# Advanced-filament-RunOut-Sensor.net
KiCad netlist of a schematic drawn in EasyEDA Pro
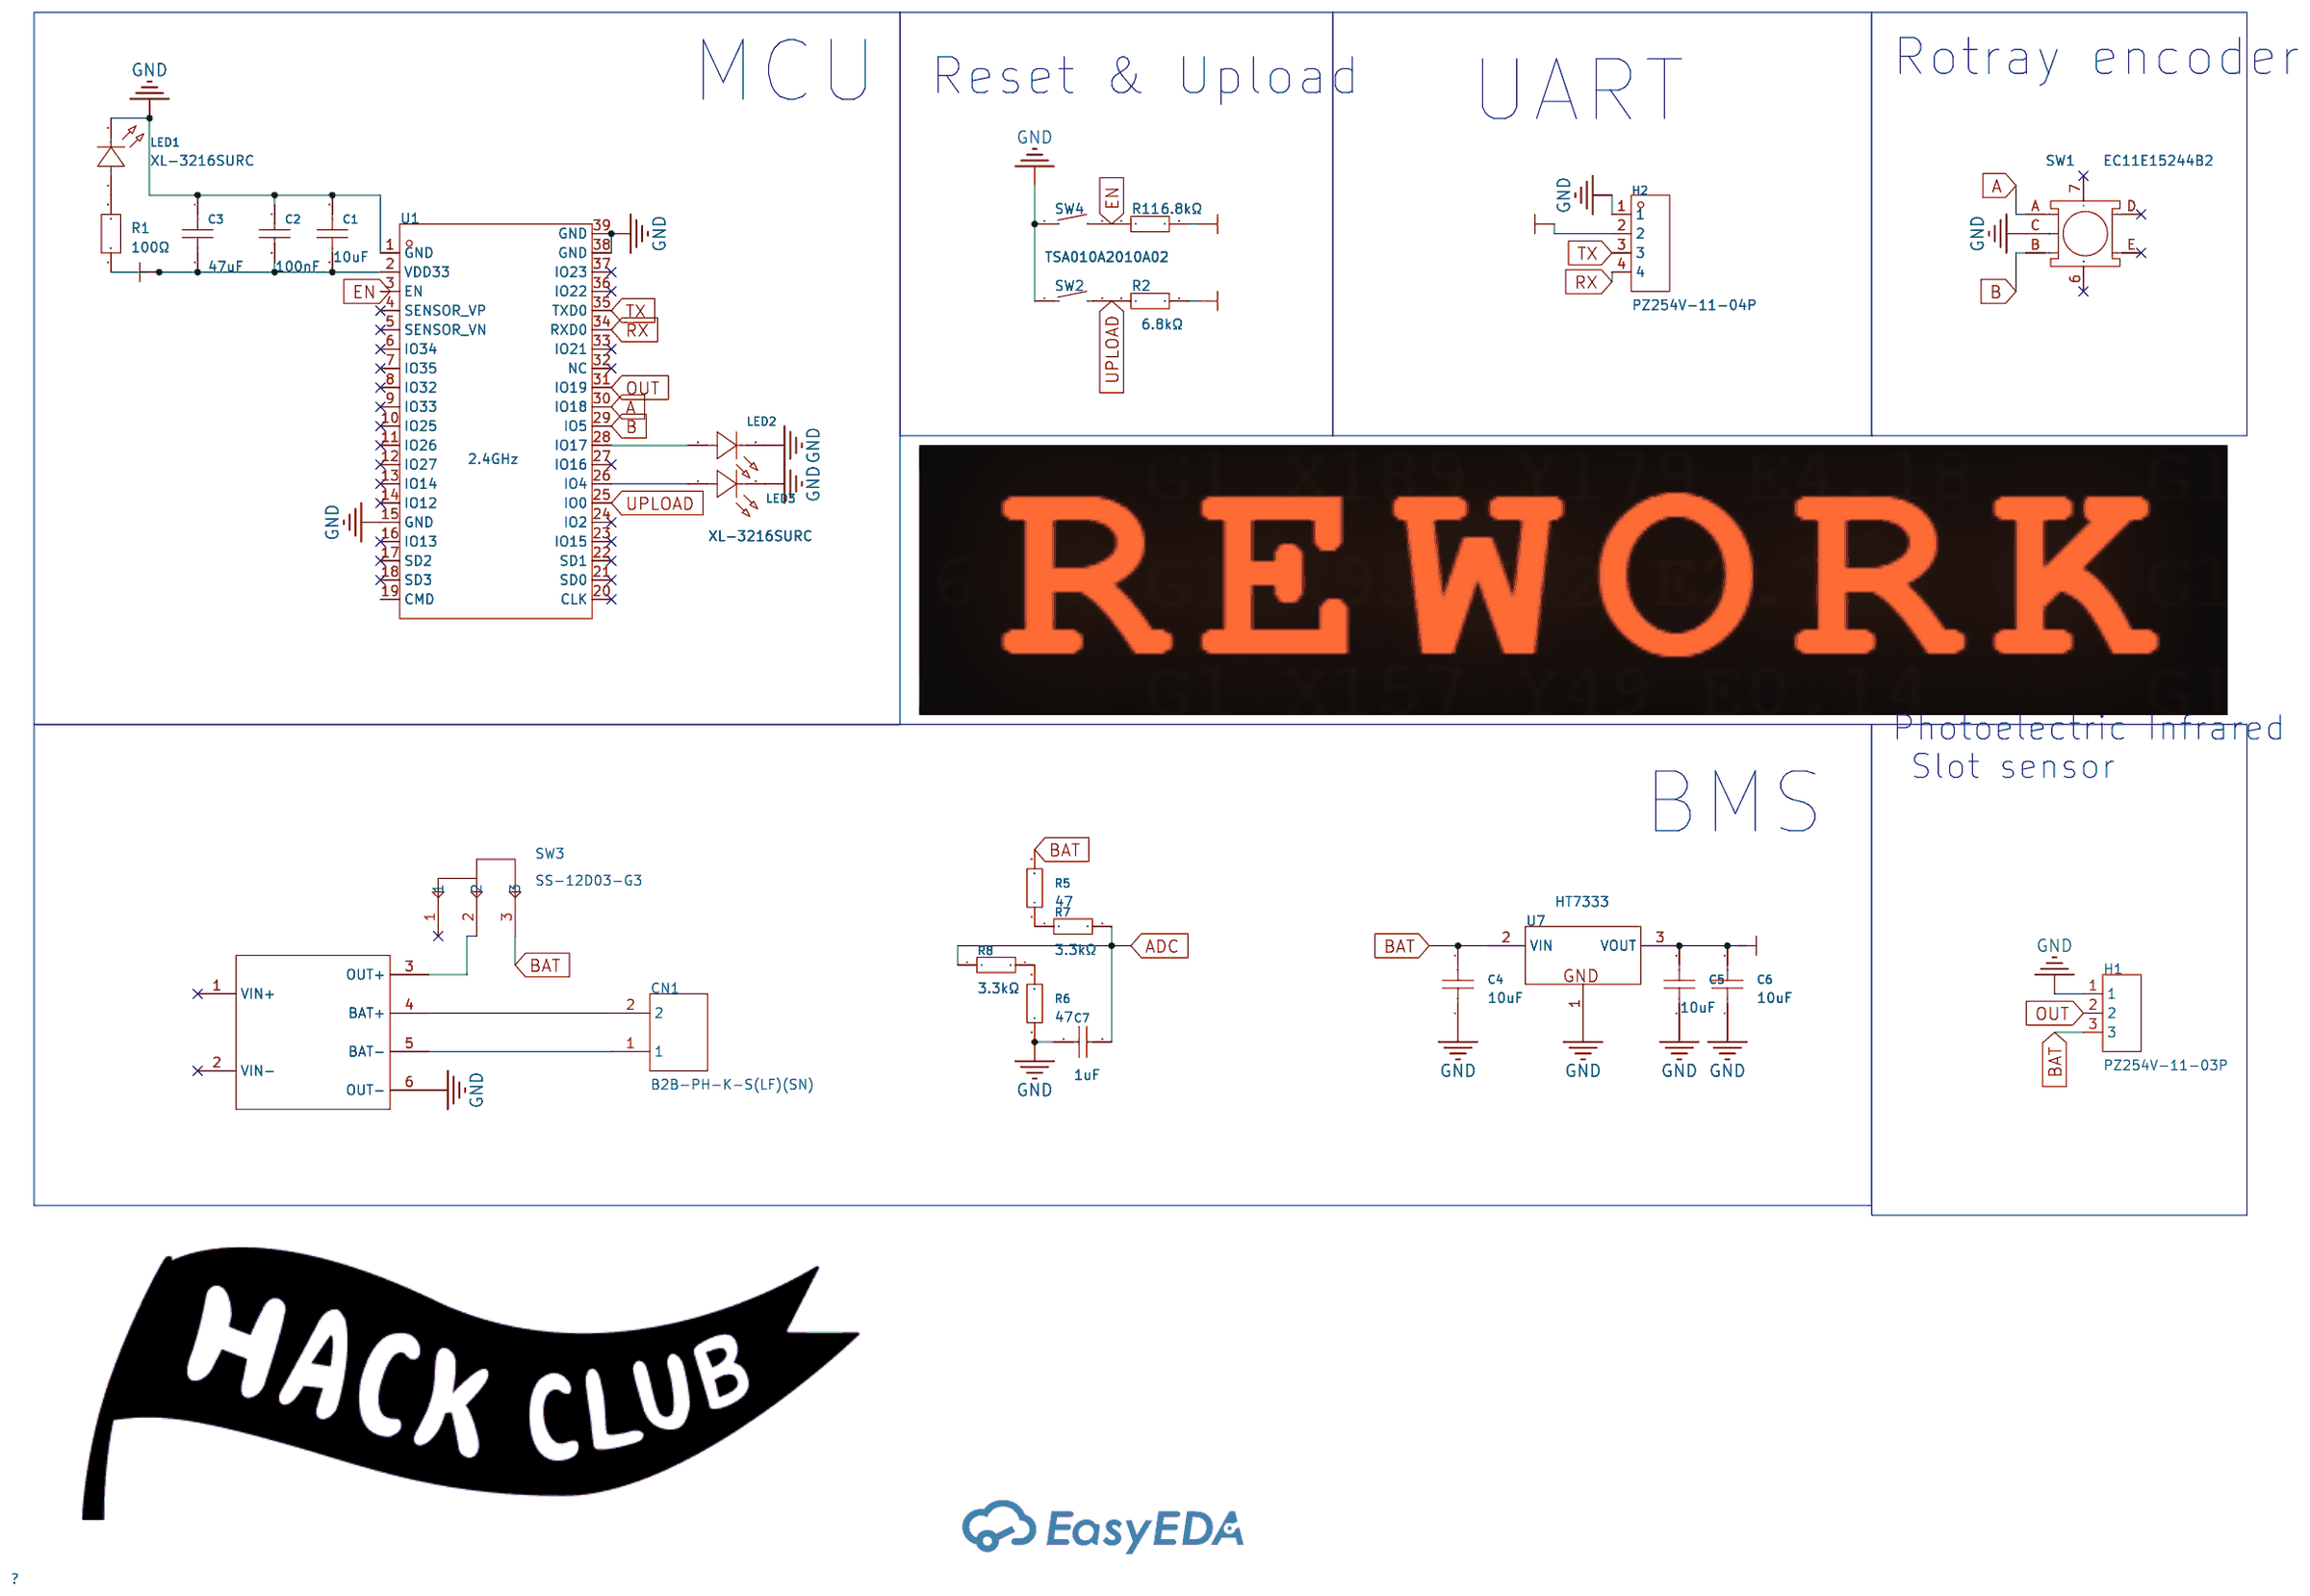
[diagram p0: schematic sheet]

(export (version "E")
  (design (tool "Eeschema 10.0.6"))
  (components
    (comp (ref "C1")
      (value "10uF")
      (footprint "easyedapro:C1206")
      (description "Capacitance:10uF Tolerance:±10% Tolerance:±10% Voltage Rating:16V Temperature Coefficient:X7R")
      (fields (field (name "Manufacturer Part") "1206B106K160CT") (field (name "Manufacturer") "Walsin(华新科)"))
      (libsource (lib "easyedapro") (part "1206B106K160"))
    )
    (comp (ref "C2")
      (value "100nF")
      (footprint "easyedapro:C1206")
      (description "Capacitance:100nF Tolerance:±10% Tolerance:±10% Voltage Rating:50V Temperature Coefficient:X7R")
      (fields
        (field (name "Manufacturer Part") "CL31B104KBCNNNC")
        (field (name "Manufacturer") "SAMSUNG(三星)")
      )
      (libsource (lib "easyedapro") (part "CL31B104KBCNNNC"))
    )
    (comp (ref "C3")
      (value "47uF")
      (footprint "easyedapro:C1206")
      (description "Capacitance:10uF Tolerance:±10% Tolerance:±10% Voltage Rating:16V Temperature Coefficient:X7R")
      (fields (field (name "Manufacturer Part") "1206B106K160CT") (field (name "Manufacturer") "Walsin(华新科)"))
      (libsource (lib "easyedapro") (part "1206B106K160"))
    )
    (comp (ref "C4")
      (value "10uF")
      (footprint "easyedapro:C0603")
      (description "Capacitance:10uF Tolerance:±20% Tolerance:±20% Voltage Rating:25V Temperature Coefficient:X5R")
      (fields
        (field (name "Manufacturer Part") "CL10A106MA8NRNC")
        (field (name "Manufacturer") "SAMSUNG(三星)")
      )
      (libsource (lib "easyedapro") (part "CL10A106MA8NRNC"))
    )
    (comp (ref "C5")
      (value "10uF")
      (footprint "easyedapro:C0603")
      (description "Capacitance:10uF Tolerance:±20% Tolerance:±20% Voltage Rating:25V Temperature Coefficient:X5R")
      (fields
        (field (name "Manufacturer Part") "CL10A106MA8NRNC")
        (field (name "Manufacturer") "SAMSUNG(三星)")
      )
      (libsource (lib "easyedapro") (part "CL10A106MA8NRNC"))
    )
    (comp (ref "C6")
      (value "10uF")
      (footprint "easyedapro:C0603")
      (description "Capacitance:10uF Tolerance:±20% Tolerance:±20% Voltage Rating:25V Temperature Coefficient:X5R")
      (fields
        (field (name "Manufacturer Part") "CL10A106MA8NRNC")
        (field (name "Manufacturer") "SAMSUNG(三星)")
      )
      (libsource (lib "easyedapro") (part "CL10A106MA8NRNC"))
    )
    (comp (ref "C7")
      (value "1uF")
      (footprint "easyedapro:C0805")
      (description "Capacitance:1uF Tolerance:±10% Tolerance:±10% Voltage Rating:50V Temperature Coefficient:X7R")
      (fields
        (field (name "Manufacturer Part") "CL21B105KBFNNNE")
        (field (name "Manufacturer") "SAMSUNG(三星)")
      )
      (libsource (lib "easyedapro") (part "CL21B105KBFNNNE"))
    )
    (comp (ref "CN1")
      (value "B2B-PH-K-S(LF)(SN)")
      (footprint "easyedapro:CONN-TH_B2B-PH-K-S")
      (fields (field (name "Manufacturer") "JST"))
      (libsource (lib "easyedapro") (part "B2B-PH-K-S(LF)(SN)"))
    )
    (comp (ref "H1")
      (value "PZ254V-11-03P")
      (footprint "easyedapro:HDR-TH_3P-P2.54-V-M_PZ254V-11-03P")
      (fields (field (name "Manufacturer") "XFCN(兴飞)"))
      (libsource (lib "easyedapro") (part "PZ254V-11-03P_C2937625"))
    )
    (comp (ref "H2")
      (value "PZ254V-11-04P")
      (footprint "easyedapro:HDR-TH_4P-P2.54-V-M")
      (fields (field (name "Manufacturer") "XFCN(兴飞)"))
      (libsource (lib "easyedapro") (part "PZ254V-11-04P_C2691448"))
    )
    (comp (ref "LED1")
      (value "XL-3216SURC")
      (footprint "easyedapro:LED1206-R-RD_RED")
      (fields (field (name "Manufacturer") "XINGLIGHT(成兴光)"))
      (libsource (lib "easyedapro") (part "XL-3216SURC"))
    )
    (comp (ref "LED2")
      (value "XL-3216SURC")
      (footprint "easyedapro:LED1206-R-RD_RED")
      (fields (field (name "Manufacturer") "XINGLIGHT(成兴光)"))
      (libsource (lib "easyedapro") (part "XL-3216SURC"))
    )
    (comp (ref "LED3")
      (value "XL-3216SURC")
      (footprint "easyedapro:LED1206-R-RD_RED")
      (fields (field (name "Manufacturer") "XINGLIGHT(成兴光)"))
      (libsource (lib "easyedapro") (part "XL-3216SURC"))
    )
    (comp (ref "R1")
      (value "100Ω")
      (footprint "easyedapro:R1206")
      (fields (field (name "Manufacturer Part") "FRC1206F1000TS") (field (name "Manufacturer") "FOJAN(富捷)"))
      (libsource (lib "easyedapro") (part "FRC1206F1000TS"))
    )
    (comp (ref "R2")
      (value "6.8kΩ")
      (footprint "easyedapro:R0603")
      (fields (field (name "Manufacturer Part") "RC0603FR-071KL") (field (name "Manufacturer") "YAGEO(国巨)"))
      (libsource (lib "easyedapro") (part "RC0603FR-071KL"))
    )
    (comp (ref "R5")
      (value "47")
      (footprint "easyedapro:R1206")
      (fields
        (field (name "Manufacturer Part") "1206W4F100KT5E")
        (field (name "Manufacturer") "UNI-ROYAL(厚声)")
      )
      (libsource (lib "easyedapro") (part "1206W4F100KT5E"))
    )
    (comp (ref "R6")
      (value "47")
      (footprint "easyedapro:R1206")
      (fields
        (field (name "Manufacturer Part") "1206W4F100KT5E")
        (field (name "Manufacturer") "UNI-ROYAL(厚声)")
      )
      (libsource (lib "easyedapro") (part "1206W4F100KT5E"))
    )
    (comp (ref "R7")
      (value "3.3kΩ")
      (footprint "easyedapro:R0603")
      (fields
        (field (name "Manufacturer Part") "0603WAF3301T5E")
        (field (name "Manufacturer") "UNI-ROYAL(厚声)")
      )
      (libsource (lib "easyedapro") (part "0603WAF3301T5E"))
    )
    (comp (ref "R8")
      (value "3.3kΩ")
      (footprint "easyedapro:R0603")
      (fields
        (field (name "Manufacturer Part") "0603WAF3301T5E")
        (field (name "Manufacturer") "UNI-ROYAL(厚声)")
      )
      (libsource (lib "easyedapro") (part "0603WAF3301T5E"))
    )
    (comp (ref "R11")
      (value "6.8kΩ")
      (footprint "easyedapro:R0603")
      (fields (field (name "Manufacturer Part") "RC0603FR-071KL") (field (name "Manufacturer") "YAGEO(国巨)"))
      (libsource (lib "easyedapro") (part "RC0603FR-071KL"))
    )
    (comp (ref "SW1")
      (value "EC11E15244B2")
      (footprint "easyedapro:SW-TH_EC11XXXXXXXX")
      (fields (field (name "Manufacturer") "ALPSALPINE(阿尔卑斯阿尔派)"))
      (libsource (lib "easyedapro") (part "EC11E15244B2"))
    )
    (comp (ref "SW2")
      (value "TSA010A2010A02")
      (footprint "easyedapro:KEY-SMD_L3.9-W3.0-LS5.0")
      (fields (field (name "Manufacturer") "BZCN(博众电气)"))
      (libsource (lib "easyedapro") (part "TSA010A2010A02"))
    )
    (comp (ref "SW3")
      (value "SS-12D03-G3")
      (footprint "easyedapro:SW-TH_3P-L8.5-W3.5-P2.50_SS-12D03-G3_C5160828")
      (fields (field (name "Manufacturer") "DEALON(德艺隆)"))
      (libsource (lib "easyedapro") (part "SS-12D03-G3_C5160828"))
    )
    (comp (ref "SW4")
      (value "TSA010A2010A02")
      (footprint "easyedapro:KEY-SMD_L3.9-W3.0-LS5.0")
      (fields (field (name "Manufacturer") "BZCN(博众电气)"))
      (libsource (lib "easyedapro") (part "TSA010A2010A02"))
    )
    (comp (ref "U1")
      (value "2.4GHz")
      (footprint "easyedapro:WIFIM-SMD_39P-L25.5-W18.0-P1.27-BL")
      (fields
        (field (name "Manufacturer Part") "ESP32-WROOM-32D-N4")
        (field (name "Manufacturer") "ESPRESSIF(乐鑫)")
      )
      (libsource (lib "easyedapro") (part "ESP32-WROOM-32D"))
    )
    (comp (ref "U6")
      (value "~")
      (footprint "easyedapro:TP4056 Carging Module")
      (libsource (lib "easyedapro") (part "TP4056 Charging Module"))
    )
    (comp (ref "U7")
      (value "HT7333")
      (footprint "easyedapro:SOT-89-3_L4.5-W2.5-P1.50-LS4.1-BR")
      (description "Output Type:-")
      (libsource (lib "easyedapro") (part "HT7333"))
    )
  )
  (nets
    (net (code "1") (name "+3V3") (class "Default")
      (node (ref "C1") (pin "2") (pinfunction "2_2") (pintype "input"))
      (node (ref "C2") (pin "2") (pinfunction "2_2") (pintype "input"))
      (node (ref "C3") (pin "2") (pinfunction "2_2") (pintype "input"))
      (node (ref "C5") (pin "2") (pinfunction "2_2") (pintype "input"))
      (node (ref "C6") (pin "2") (pinfunction "2_2") (pintype "input"))
      (node (ref "H2") (pin "2") (pinfunction "2_2") (pintype "input"))
      (node (ref "R1") (pin "1") (pinfunction "1_1") (pintype "unspecified"))
      (node (ref "R11") (pin "2") (pinfunction "2_2") (pintype "input"))
      (node (ref "R2") (pin "2") (pinfunction "2_2") (pintype "input"))
      (node (ref "U1") (pin "2") (pinfunction "VDD33_2") (pintype "unspecified"))
      (node (ref "U7") (pin "3") (pinfunction "VOUT_3") (pintype "unspecified"))
    )
    (net (code "2") (name "A") (class "Default")
      (node (ref "SW1") (pin "A") (pinfunction "A_A") (pintype "unspecified"))
      (node (ref "U1") (pin "30") (pinfunction "IO18_30") (pintype "unspecified"))
    )
    (net (code "3") (name "ADC") (class "Default")
      (node (ref "C7") (pin "2") (pinfunction "2_2") (pintype "input"))
      (node (ref "R7") (pin "2") (pinfunction "2_2") (pintype "input"))
      (node (ref "R8") (pin "1") (pinfunction "1_1") (pintype "input"))
    )
    (net (code "4") (name "B") (class "Default")
      (node (ref "SW1") (pin "B") (pinfunction "B_B") (pintype "unspecified"))
      (node (ref "U1") (pin "29") (pinfunction "IO5_29") (pintype "unspecified"))
    )
    (net (code "5") (name "BAT") (class "Default")
      (node (ref "C4") (pin "2") (pinfunction "2_2") (pintype "input"))
      (node (ref "H1") (pin "3") (pinfunction "3_3") (pintype "unspecified"))
      (node (ref "R5") (pin "2") (pinfunction "2_2") (pintype "input"))
      (node (ref "SW3") (pin "3") (pinfunction "3_3") (pintype "unspecified"))
      (node (ref "U7") (pin "2") (pinfunction "VIN_2") (pintype "unspecified"))
    )
    (net (code "6") (name "EN") (class "Default")
      (node (ref "R11") (pin "1") (pinfunction "1_1") (pintype "input"))
      (node (ref "SW4") (pin "2") (pinfunction "2_2") (pintype "unspecified"))
      (node (ref "U1") (pin "3") (pinfunction "EN_3") (pintype "unspecified"))
    )
    (net (code "7") (name "GND") (class "Default")
      (node (ref "C1") (pin "1") (pinfunction "1_1") (pintype "input"))
      (node (ref "C2") (pin "1") (pinfunction "1_1") (pintype "input"))
      (node (ref "C3") (pin "1") (pinfunction "1_1") (pintype "input"))
      (node (ref "C4") (pin "1") (pinfunction "1_1") (pintype "input"))
      (node (ref "C5") (pin "1") (pinfunction "1_1") (pintype "input"))
      (node (ref "C6") (pin "1") (pinfunction "1_1") (pintype "input"))
      (node (ref "C7") (pin "1") (pinfunction "1_1") (pintype "input"))
      (node (ref "H1") (pin "1") (pinfunction "1_1") (pintype "unspecified"))
      (node (ref "H2") (pin "1") (pinfunction "1_1") (pintype "input"))
      (node (ref "LED1") (pin "2") (pinfunction "A_2") (pintype "input"))
      (node (ref "LED2") (pin "2") (pinfunction "A_2") (pintype "input"))
      (node (ref "LED3") (pin "2") (pinfunction "A_2") (pintype "input"))
      (node (ref "R6") (pin "1") (pinfunction "1_1") (pintype "input"))
      (node (ref "SW1") (pin "C") (pinfunction "C_C") (pintype "unspecified"))
      (node (ref "SW2") (pin "1") (pinfunction "1_1") (pintype "unspecified"))
      (node (ref "SW4") (pin "1") (pinfunction "1_1") (pintype "unspecified"))
      (node (ref "U1") (pin "1") (pinfunction "GND_1") (pintype "unspecified"))
      (node (ref "U1") (pin "15") (pinfunction "GND_15") (pintype "unspecified"))
      (node (ref "U1") (pin "38") (pinfunction "GND_38") (pintype "unspecified"))
      (node (ref "U1") (pin "39") (pinfunction "GND_39") (pintype "unspecified"))
      (node (ref "U6") (pin "6") (pinfunction "OUT-_6") (pintype "input"))
      (node (ref "U7") (pin "1") (pinfunction "GND_1") (pintype "unspecified"))
    )
    (net (code "8") (name "Net-(LED1-K)") (class "Default")
      (node (ref "LED1") (pin "1") (pinfunction "K_1") (pintype "input"))
      (node (ref "R1") (pin "2") (pinfunction "2_2") (pintype "unspecified"))
    )
    (net (code "9") (name "Net-(LED2-K)") (class "Default")
      (node (ref "LED2") (pin "1") (pinfunction "K_1") (pintype "input"))
      (node (ref "U1") (pin "28") (pinfunction "IO17_28") (pintype "unspecified"))
    )
    (net (code "10") (name "Net-(LED3-K)") (class "Default")
      (node (ref "LED3") (pin "1") (pinfunction "K_1") (pintype "input"))
      (node (ref "U1") (pin "26") (pinfunction "IO4_26") (pintype "unspecified"))
    )
    (net (code "11") (name "Net-(R5-Pad1)") (class "Default")
      (node (ref "R5") (pin "1") (pinfunction "1_1") (pintype "input"))
      (node (ref "R7") (pin "1") (pinfunction "1_1") (pintype "input"))
    )
    (net (code "12") (name "Net-(R6-Pad2)") (class "Default")
      (node (ref "R6") (pin "2") (pinfunction "2_2") (pintype "input"))
      (node (ref "R8") (pin "2") (pinfunction "2_2") (pintype "input"))
    )
    (net (code "13") (name "Net-(U6-BAT+)") (class "Default")
      (node (ref "CN1") (pin "2") (pinfunction "2_2") (pintype "input"))
      (node (ref "U6") (pin "4") (pinfunction "BAT+_4") (pintype "input"))
    )
    (net (code "14") (name "Net-(U6-BAT-)") (class "Default")
      (node (ref "CN1") (pin "1") (pinfunction "1_1") (pintype "input"))
      (node (ref "U6") (pin "5") (pinfunction "BAT-_5") (pintype "input"))
    )
    (net (code "15") (name "Net-(U6-OUT+)") (class "Default")
      (node (ref "SW3") (pin "2") (pinfunction "2_2") (pintype "unspecified"))
      (node (ref "U6") (pin "3") (pinfunction "OUT+_3") (pintype "input"))
    )
    (net (code "16") (name "OUT") (class "Default")
      (node (ref "H1") (pin "2") (pinfunction "2_2") (pintype "unspecified"))
      (node (ref "U1") (pin "31") (pinfunction "IO19_31") (pintype "unspecified"))
    )
    (net (code "17") (name "RX") (class "Default")
      (node (ref "H2") (pin "4") (pinfunction "4_4") (pintype "input"))
      (node (ref "U1") (pin "34") (pinfunction "RXD0_34") (pintype "unspecified"))
    )
    (net (code "18") (name "TX") (class "Default")
      (node (ref "H2") (pin "3") (pinfunction "3_3") (pintype "input"))
      (node (ref "U1") (pin "35") (pinfunction "TXD0_35") (pintype "unspecified"))
    )
    (net (code "19") (name "UPLOAD") (class "Default")
      (node (ref "R2") (pin "1") (pinfunction "1_1") (pintype "input"))
      (node (ref "SW2") (pin "2") (pinfunction "2_2") (pintype "unspecified"))
      (node (ref "U1") (pin "25") (pinfunction "IO0_25") (pintype "unspecified"))
    )
    (net (code "20") (name "unconnected-(SW1-Pad6)") (class "Default")
      (node (ref "SW1") (pin "6") (pinfunction "6_6") (pintype "unspecified+no_connect"))
    )
    (net (code "21") (name "unconnected-(SW1-Pad7)") (class "Default")
      (node (ref "SW1") (pin "7") (pinfunction "7_7") (pintype "unspecified+no_connect"))
    )
    (net (code "22") (name "unconnected-(SW1-PadD)") (class "Default")
      (node (ref "SW1") (pin "D") (pinfunction "D_D") (pintype "unspecified+no_connect"))
    )
    (net (code "23") (name "unconnected-(SW1-PadE)") (class "Default")
      (node (ref "SW1") (pin "E") (pinfunction "E_E") (pintype "unspecified+no_connect"))
    )
    (net (code "24") (name "unconnected-(SW3-Pad1)") (class "Default")
      (node (ref "SW3") (pin "1") (pinfunction "1_1") (pintype "unspecified+no_connect"))
    )
    (net (code "25") (name "unconnected-(U1-CLK-Pad20)") (class "Default")
      (node (ref "U1") (pin "20") (pinfunction "CLK_20") (pintype "unspecified+no_connect"))
    )
    (net (code "26") (name "unconnected-(U1-CMD-Pad19)") (class "Default")
      (node (ref "U1") (pin "19") (pinfunction "CMD_19") (pintype "unspecified"))
    )
    (net (code "27") (name "unconnected-(U1-IO2-Pad24)") (class "Default")
      (node (ref "U1") (pin "24") (pinfunction "IO2_24") (pintype "unspecified+no_connect"))
    )
    (net (code "28") (name "unconnected-(U1-IO12-Pad14)") (class "Default")
      (node (ref "U1") (pin "14") (pinfunction "IO12_14") (pintype "unspecified+no_connect"))
    )
    (net (code "29") (name "unconnected-(U1-IO13-Pad16)") (class "Default")
      (node (ref "U1") (pin "16") (pinfunction "IO13_16") (pintype "unspecified+no_connect"))
    )
    (net (code "30") (name "unconnected-(U1-IO14-Pad13)") (class "Default")
      (node (ref "U1") (pin "13") (pinfunction "IO14_13") (pintype "unspecified+no_connect"))
    )
    (net (code "31") (name "unconnected-(U1-IO15-Pad23)") (class "Default")
      (node (ref "U1") (pin "23") (pinfunction "IO15_23") (pintype "unspecified+no_connect"))
    )
    (net (code "32") (name "unconnected-(U1-IO16-Pad27)") (class "Default")
      (node (ref "U1") (pin "27") (pinfunction "IO16_27") (pintype "unspecified+no_connect"))
    )
    (net (code "33") (name "unconnected-(U1-IO21-Pad33)") (class "Default")
      (node (ref "U1") (pin "33") (pinfunction "IO21_33") (pintype "unspecified+no_connect"))
    )
    (net (code "34") (name "unconnected-(U1-IO22-Pad36)") (class "Default")
      (node (ref "U1") (pin "36") (pinfunction "IO22_36") (pintype "unspecified+no_connect"))
    )
    (net (code "35") (name "unconnected-(U1-IO23-Pad37)") (class "Default")
      (node (ref "U1") (pin "37") (pinfunction "IO23_37") (pintype "unspecified+no_connect"))
    )
    (net (code "36") (name "unconnected-(U1-IO25-Pad10)") (class "Default")
      (node (ref "U1") (pin "10") (pinfunction "IO25_10") (pintype "unspecified+no_connect"))
    )
    (net (code "37") (name "unconnected-(U1-IO26-Pad11)") (class "Default")
      (node (ref "U1") (pin "11") (pinfunction "IO26_11") (pintype "unspecified+no_connect"))
    )
    (net (code "38") (name "unconnected-(U1-IO27-Pad12)") (class "Default")
      (node (ref "U1") (pin "12") (pinfunction "IO27_12") (pintype "unspecified+no_connect"))
    )
    (net (code "39") (name "unconnected-(U1-IO32-Pad8)") (class "Default")
      (node (ref "U1") (pin "8") (pinfunction "IO32_8") (pintype "unspecified+no_connect"))
    )
    (net (code "40") (name "unconnected-(U1-IO33-Pad9)") (class "Default")
      (node (ref "U1") (pin "9") (pinfunction "IO33_9") (pintype "unspecified+no_connect"))
    )
    (net (code "41") (name "unconnected-(U1-IO34-Pad6)") (class "Default")
      (node (ref "U1") (pin "6") (pinfunction "IO34_6") (pintype "unspecified+no_connect"))
    )
    (net (code "42") (name "unconnected-(U1-IO35-Pad7)") (class "Default")
      (node (ref "U1") (pin "7") (pinfunction "IO35_7") (pintype "unspecified+no_connect"))
    )
    (net (code "43") (name "unconnected-(U1-NC-Pad32)") (class "Default")
      (node (ref "U1") (pin "32") (pinfunction "NC_32") (pintype "unspecified+no_connect"))
    )
    (net (code "44") (name "unconnected-(U1-SD0-Pad21)") (class "Default")
      (node (ref "U1") (pin "21") (pinfunction "SD0_21") (pintype "unspecified+no_connect"))
    )
    (net (code "45") (name "unconnected-(U1-SD1-Pad22)") (class "Default")
      (node (ref "U1") (pin "22") (pinfunction "SD1_22") (pintype "unspecified+no_connect"))
    )
    (net (code "46") (name "unconnected-(U1-SD2-Pad17)") (class "Default")
      (node (ref "U1") (pin "17") (pinfunction "SD2_17") (pintype "unspecified+no_connect"))
    )
    (net (code "47") (name "unconnected-(U1-SD3-Pad18)") (class "Default")
      (node (ref "U1") (pin "18") (pinfunction "SD3_18") (pintype "unspecified+no_connect"))
    )
    (net (code "48") (name "unconnected-(U1-SENSOR_VN-Pad5)") (class "Default")
      (node (ref "U1") (pin "5") (pinfunction "SENSOR_VN_5") (pintype "unspecified+no_connect"))
    )
    (net (code "49") (name "unconnected-(U1-SENSOR_VP-Pad4)") (class "Default")
      (node (ref "U1") (pin "4") (pinfunction "SENSOR_VP_4") (pintype "unspecified+no_connect"))
    )
    (net (code "50") (name "unconnected-(U6-VIN+-Pad1)") (class "Default")
      (node (ref "U6") (pin "1") (pinfunction "VIN+_1") (pintype "input+no_connect"))
    )
    (net (code "51") (name "unconnected-(U6-VIN--Pad2)") (class "Default")
      (node (ref "U6") (pin "2") (pinfunction "VIN-_2") (pintype "input+no_connect"))
    )
  )
)
